# main.net
KiCad netlist of a schematic drawn in EAGLE
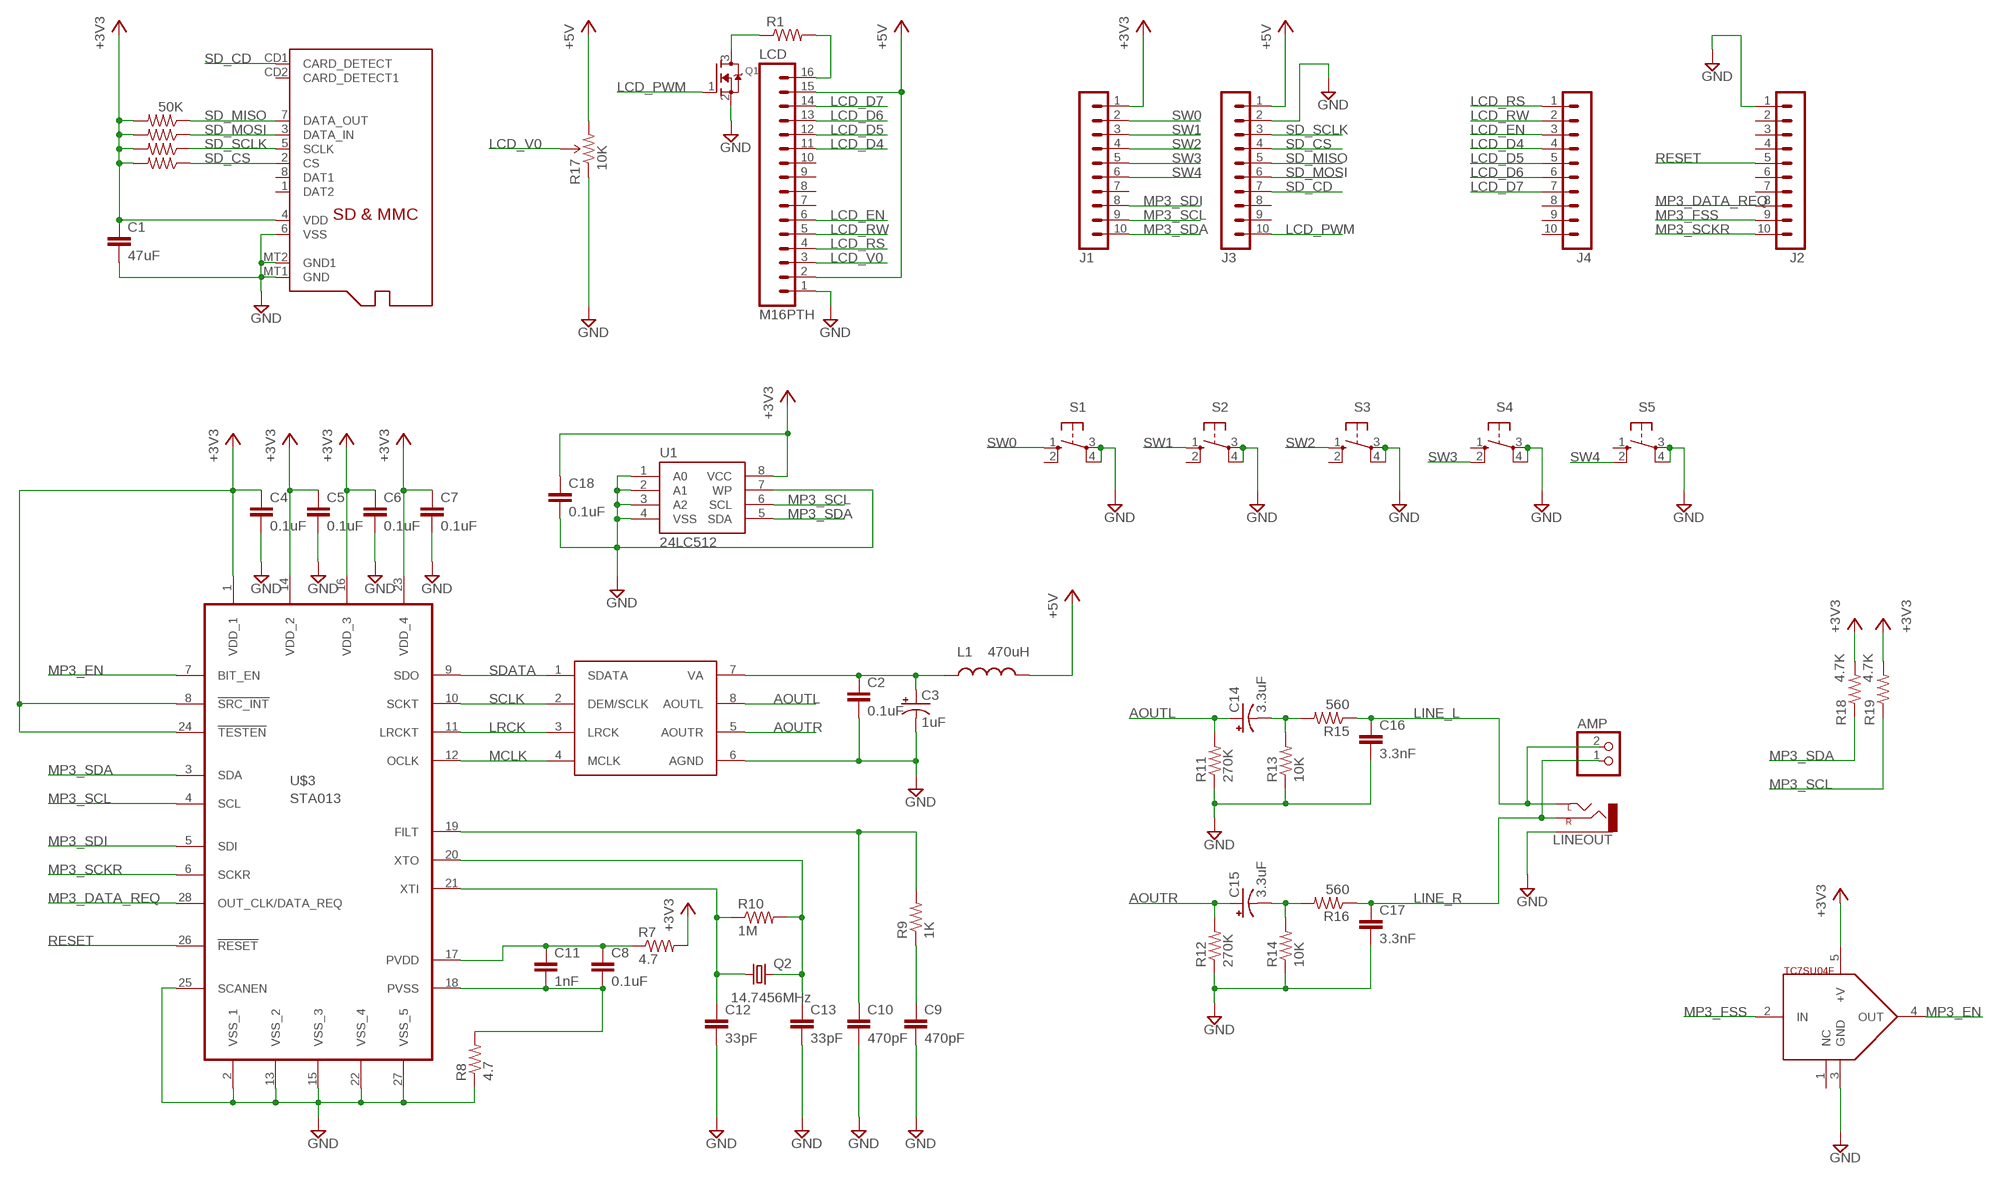
[diagram p0: schematic, sheet 1]

(export (version "E")
  (design (tool "Eeschema 10.0.6"))
  (components
    (comp (ref "AMP")
      (value "JST_2PIN-THM-RA")
      (footprint "eagle-import:JST-PH-2-THM-RA")
      (libsource (lib "eagle-import") (part "JST_2PIN-THM-RA"))
    )
    (comp (ref "C1")
      (value "47uF")
      (footprint "eagle-import:0805")
      (libsource (lib "eagle-import") (part "1.0UF-25V-+80/-20(0805)"))
    )
    (comp (ref "C2")
      (value "0.1uF")
      (footprint "eagle-import:0805")
      (libsource (lib "eagle-import") (part "1.0UF-25V-+80/-20(0805)"))
    )
    (comp (ref "C3")
      (value "1uF")
      (footprint "eagle-import:EIA3216")
      (libsource (lib "eagle-import") (part "CAP_POL1206"))
    )
    (comp (ref "C4")
      (value "0.1uF")
      (footprint "eagle-import:0805")
      (libsource (lib "eagle-import") (part "1.0UF-25V-+80/-20(0805)"))
    )
    (comp (ref "C5")
      (value "0.1uF")
      (footprint "eagle-import:0805")
      (libsource (lib "eagle-import") (part "1.0UF-25V-+80/-20(0805)"))
    )
    (comp (ref "C6")
      (value "0.1uF")
      (footprint "eagle-import:0805")
      (libsource (lib "eagle-import") (part "1.0UF-25V-+80/-20(0805)"))
    )
    (comp (ref "C7")
      (value "0.1uF")
      (footprint "eagle-import:0805")
      (libsource (lib "eagle-import") (part "1.0UF-25V-+80/-20(0805)"))
    )
    (comp (ref "C8")
      (value "0.1uF")
      (footprint "eagle-import:0805")
      (libsource (lib "eagle-import") (part "1.0UF-25V-+80/-20(0805)"))
    )
    (comp (ref "C9")
      (value "470pF")
      (footprint "eagle-import:0805")
      (libsource (lib "eagle-import") (part "1.0UF-25V-+80/-20(0805)"))
    )
    (comp (ref "C10")
      (value "470pF")
      (footprint "eagle-import:0805")
      (libsource (lib "eagle-import") (part "1.0UF-25V-+80/-20(0805)"))
    )
    (comp (ref "C11")
      (value "1nF")
      (footprint "eagle-import:0805")
      (libsource (lib "eagle-import") (part "1.0UF-25V-+80/-20(0805)"))
    )
    (comp (ref "C12")
      (value "33pF")
      (footprint "eagle-import:0805")
      (libsource (lib "eagle-import") (part "1.0UF-25V-+80/-20(0805)"))
    )
    (comp (ref "C13")
      (value "33pF")
      (footprint "eagle-import:0805")
      (libsource (lib "eagle-import") (part "1.0UF-25V-+80/-20(0805)"))
    )
    (comp (ref "C14")
      (value "3.3uF")
      (footprint "eagle-import:EIA3216")
      (libsource (lib "eagle-import") (part "CAP_POL1206"))
    )
    (comp (ref "C15")
      (value "3.3uF")
      (footprint "eagle-import:EIA3216")
      (libsource (lib "eagle-import") (part "CAP_POL1206"))
    )
    (comp (ref "C16")
      (value "3.3nF")
      (footprint "eagle-import:0805")
      (libsource (lib "eagle-import") (part "1.0UF-25V-+80/-20(0805)"))
    )
    (comp (ref "C17")
      (value "3.3nF")
      (footprint "eagle-import:0805")
      (libsource (lib "eagle-import") (part "1.0UF-25V-+80/-20(0805)"))
    )
    (comp (ref "C18")
      (value "0.1uF")
      (footprint "eagle-import:0805")
      (libsource (lib "eagle-import") (part "1.0UF-25V-+80/-20(0805)"))
    )
    (comp (ref "J1")
      (value "MA10-1")
      (footprint "eagle-import:HEADER-10")
      (libsource (lib "eagle-import") (part "MA10-1"))
    )
    (comp (ref "J2")
      (value "MA10-1")
      (footprint "eagle-import:HEADER-10")
      (libsource (lib "eagle-import") (part "MA10-1"))
    )
    (comp (ref "J3")
      (value "MA10-1")
      (footprint "eagle-import:HEADER-10")
      (libsource (lib "eagle-import") (part "MA10-1"))
    )
    (comp (ref "J4")
      (value "MA10-1")
      (footprint "eagle-import:HEADER-10")
      (libsource (lib "eagle-import") (part "MA10-1"))
    )
    (comp (ref "L1")
      (value "470uH")
      (footprint "eagle-import:SRR7032")
      (libsource (lib "eagle-import") (part "INDUCTORSRR7032"))
    )
    (comp (ref "LCD")
      (value "M16PTH")
      (footprint "eagle-import:1X16")
      (libsource (lib "eagle-import") (part "M16PTH"))
    )
    (comp (ref "LINEOUT")
      (value "AUDIO-JACKPTH")
      (footprint "eagle-import:AUDIO-JACK")
      (libsource (lib "eagle-import") (part "AUDIO-JACKPTH"))
    )
    (comp (ref "Q1")
      (value "MOSFET-NREFLOW")
      (footprint "eagle-import:SOT23")
      (libsource (lib "eagle-import") (part "MOSFET-NREFLOW"))
    )
    (comp (ref "Q2")
      (value "14.7456MHz")
      (footprint "eagle-import:HC49UP")
      (libsource (lib "eagle-import") (part "CRYSTALHC49UP"))
    )
    (comp (ref "R1")
      (value "R-US_R0805")
      (footprint "eagle-import:R0805")
      (libsource (lib "eagle-import") (part "R-US_R0805"))
    )
    (comp (ref "R3")
      (value "50K")
      (footprint "eagle-import:R0805")
      (libsource (lib "eagle-import") (part "R-US_R0805"))
    )
    (comp (ref "R4")
      (value "50K")
      (footprint "eagle-import:R0805")
      (libsource (lib "eagle-import") (part "R-US_R0805"))
    )
    (comp (ref "R5")
      (value "50K")
      (footprint "eagle-import:R0805")
      (libsource (lib "eagle-import") (part "R-US_R0805"))
    )
    (comp (ref "R6")
      (value "50K")
      (footprint "eagle-import:R0805")
      (libsource (lib "eagle-import") (part "R-US_R0805"))
    )
    (comp (ref "R7")
      (value "4.7")
      (footprint "eagle-import:R0805")
      (libsource (lib "eagle-import") (part "R-US_R0805"))
    )
    (comp (ref "R8")
      (value "4.7")
      (footprint "eagle-import:R0805")
      (libsource (lib "eagle-import") (part "R-US_R0805"))
    )
    (comp (ref "R9")
      (value "1K")
      (footprint "eagle-import:R0805")
      (libsource (lib "eagle-import") (part "R-US_R0805"))
    )
    (comp (ref "R10")
      (value "1M")
      (footprint "eagle-import:R0805")
      (libsource (lib "eagle-import") (part "R-US_R0805"))
    )
    (comp (ref "R11")
      (value "270K")
      (footprint "eagle-import:R0805")
      (libsource (lib "eagle-import") (part "R-US_R0805"))
    )
    (comp (ref "R12")
      (value "270K")
      (footprint "eagle-import:R0805")
      (libsource (lib "eagle-import") (part "R-US_R0805"))
    )
    (comp (ref "R13")
      (value "10K")
      (footprint "eagle-import:R0805")
      (libsource (lib "eagle-import") (part "R-US_R0805"))
    )
    (comp (ref "R14")
      (value "10K")
      (footprint "eagle-import:R0805")
      (libsource (lib "eagle-import") (part "R-US_R0805"))
    )
    (comp (ref "R15")
      (value "560")
      (footprint "eagle-import:R0805")
      (libsource (lib "eagle-import") (part "R-US_R0805"))
    )
    (comp (ref "R16")
      (value "560")
      (footprint "eagle-import:R0805")
      (libsource (lib "eagle-import") (part "R-US_R0805"))
    )
    (comp (ref "R17")
      (value "10K")
      (footprint "eagle-import:3364W")
      (libsource (lib "eagle-import") (part "TRIMPOT3364W"))
    )
    (comp (ref "R18")
      (value "4.7K")
      (footprint "eagle-import:R0805")
      (libsource (lib "eagle-import") (part "R-US_R0805"))
    )
    (comp (ref "R19")
      (value "4.7K")
      (footprint "eagle-import:R0805")
      (libsource (lib "eagle-import") (part "R-US_R0805"))
    )
    (comp (ref "S1")
      (value "10-XX")
      (footprint "eagle-import:B3F-10XX")
      (fields (field (name "MPN") "B3F-1000"))
      (libsource (lib "eagle-import") (part "10-XX"))
    )
    (comp (ref "S2")
      (value "10-XX")
      (footprint "eagle-import:B3F-10XX")
      (fields (field (name "MPN") "B3F-1000"))
      (libsource (lib "eagle-import") (part "10-XX"))
    )
    (comp (ref "S3")
      (value "10-XX")
      (footprint "eagle-import:B3F-10XX")
      (fields (field (name "MPN") "B3F-1000"))
      (libsource (lib "eagle-import") (part "10-XX"))
    )
    (comp (ref "S4")
      (value "10-XX")
      (footprint "eagle-import:B3F-10XX")
      (fields (field (name "MPN") "B3F-1000"))
      (libsource (lib "eagle-import") (part "10-XX"))
    )
    (comp (ref "S5")
      (value "10-XX")
      (footprint "eagle-import:B3F-10XX")
      (fields (field (name "MPN") "B3F-1000"))
      (libsource (lib "eagle-import") (part "10-XX"))
    )
    (comp (ref "U$1")
      (value "MICROSD")
      (footprint "eagle-import:MICROSD")
      (libsource (lib "eagle-import") (part "MICROSD"))
    )
    (comp (ref "U$2")
      (value "CS4334")
      (footprint "eagle-import:SO08")
      (libsource (lib "eagle-import") (part "CS4334"))
    )
    (comp (ref "U$3")
      (value "STA013")
      (footprint "eagle-import:SO28W")
      (libsource (lib "eagle-import") (part "STA013"))
    )
    (comp (ref "U$4")
      (value "TC7SU04F")
      (footprint "eagle-import:SOT23-5")
      (libsource (lib "eagle-import") (part "TC7SU04F"))
    )
    (comp (ref "U1")
      (value "24LC512")
      (footprint "eagle-import:SO08")
      (libsource (lib "eagle-import") (part "EEPROM-I2CSMD"))
    )
  )
  (nets
    (net (code "1") (name "+3V3") (class "Default")
      (node (ref "C1") (pin "1") (pinfunction "1_1") (pintype "passive"))
      (node (ref "C18") (pin "1") (pinfunction "1_1") (pintype "passive"))
      (node (ref "C4") (pin "1") (pinfunction "1_1") (pintype "passive"))
      (node (ref "C5") (pin "1") (pinfunction "1_1") (pintype "passive"))
      (node (ref "C6") (pin "1") (pinfunction "1_1") (pintype "passive"))
      (node (ref "C7") (pin "1") (pinfunction "1_1") (pintype "passive"))
      (node (ref "J1") (pin "1") (pinfunction "1_1") (pintype "passive"))
      (node (ref "R18") (pin "2") (pinfunction "2_2") (pintype "passive"))
      (node (ref "R19") (pin "2") (pinfunction "2_2") (pintype "passive"))
      (node (ref "R3") (pin "2") (pinfunction "2_2") (pintype "passive"))
      (node (ref "R4") (pin "2") (pinfunction "2_2") (pintype "passive"))
      (node (ref "R5") (pin "2") (pinfunction "2_2") (pintype "passive"))
      (node (ref "R6") (pin "2") (pinfunction "2_2") (pintype "passive"))
      (node (ref "R7") (pin "2") (pinfunction "2_2") (pintype "passive"))
      (node (ref "U$1") (pin "4") (pinfunction "VDD_4") (pintype "power_in"))
      (node (ref "U$3") (pin "1") (pinfunction "VDD_1_1") (pintype "bidirectional"))
      (node (ref "U$3") (pin "14") (pinfunction "VDD_2_14") (pintype "bidirectional"))
      (node (ref "U$3") (pin "16") (pinfunction "VDD_3_16") (pintype "bidirectional"))
      (node (ref "U$3") (pin "23") (pinfunction "VDD_4_23") (pintype "bidirectional"))
      (node (ref "U$3") (pin "24") (pinfunction "~{TESTEN}_24") (pintype "bidirectional"))
      (node (ref "U$3") (pin "8") (pinfunction "~{SRC_INT}_8") (pintype "bidirectional"))
      (node (ref "U$4") (pin "5") (pinfunction "+V_5") (pintype "bidirectional"))
      (node (ref "U1") (pin "8") (pinfunction "VCC_8") (pintype "power_in"))
    )
    (net (code "2") (name "+5V") (class "Default")
      (node (ref "J3") (pin "1") (pinfunction "1_1") (pintype "passive"))
      (node (ref "L1") (pin "P$2") (pinfunction "2_P$2") (pintype "passive"))
      (node (ref "LCD") (pin "15") (pinfunction "15_15") (pintype "passive"))
      (node (ref "LCD") (pin "2") (pinfunction "2_2") (pintype "passive"))
      (node (ref "R17") (pin "3") (pinfunction "CW_3") (pintype "passive"))
    )
    (net (code "3") (name "/AOUTL") (class "Default")
      (node (ref "C14") (pin "A") (pinfunction "+_A") (pintype "passive"))
      (node (ref "R11") (pin "2") (pinfunction "2_2") (pintype "passive"))
      (node (ref "U$2") (pin "8") (pinfunction "AOUTL_8") (pintype "bidirectional"))
    )
    (net (code "4") (name "/AOUTR") (class "Default")
      (node (ref "C15") (pin "A") (pinfunction "+_A") (pintype "passive"))
      (node (ref "R12") (pin "2") (pinfunction "2_2") (pintype "passive"))
      (node (ref "U$2") (pin "5") (pinfunction "AOUTR_5") (pintype "bidirectional"))
    )
    (net (code "5") (name "/LCD_D4") (class "Default")
      (node (ref "J4") (pin "4") (pinfunction "4_4") (pintype "passive"))
      (node (ref "LCD") (pin "11") (pinfunction "11_11") (pintype "passive"))
    )
    (net (code "6") (name "/LCD_D5") (class "Default")
      (node (ref "J4") (pin "5") (pinfunction "5_5") (pintype "passive"))
      (node (ref "LCD") (pin "12") (pinfunction "12_12") (pintype "passive"))
    )
    (net (code "7") (name "/LCD_D6") (class "Default")
      (node (ref "J4") (pin "6") (pinfunction "6_6") (pintype "passive"))
      (node (ref "LCD") (pin "13") (pinfunction "13_13") (pintype "passive"))
    )
    (net (code "8") (name "/LCD_D7") (class "Default")
      (node (ref "J4") (pin "7") (pinfunction "7_7") (pintype "passive"))
      (node (ref "LCD") (pin "14") (pinfunction "14_14") (pintype "passive"))
    )
    (net (code "9") (name "/LCD_EN") (class "Default")
      (node (ref "J4") (pin "3") (pinfunction "3_3") (pintype "passive"))
      (node (ref "LCD") (pin "6") (pinfunction "6_6") (pintype "passive"))
    )
    (net (code "10") (name "/LCD_PWM") (class "Default")
      (node (ref "J3") (pin "10") (pinfunction "10_10") (pintype "passive"))
      (node (ref "Q1") (pin "1") (pinfunction "G_1") (pintype "bidirectional"))
    )
    (net (code "11") (name "/LCD_RS") (class "Default")
      (node (ref "J4") (pin "1") (pinfunction "1_1") (pintype "passive"))
      (node (ref "LCD") (pin "4") (pinfunction "4_4") (pintype "passive"))
    )
    (net (code "12") (name "/LCD_RW") (class "Default")
      (node (ref "J4") (pin "2") (pinfunction "2_2") (pintype "passive"))
      (node (ref "LCD") (pin "5") (pinfunction "5_5") (pintype "passive"))
    )
    (net (code "13") (name "/LCD_V0") (class "Default")
      (node (ref "LCD") (pin "3") (pinfunction "3_3") (pintype "passive"))
      (node (ref "R17") (pin "2") (pinfunction "WIPER_2") (pintype "passive"))
    )
    (net (code "14") (name "/LINE_L") (class "Default")
      (node (ref "AMP") (pin "2") (pinfunction "1_2") (pintype "passive"))
      (node (ref "C16") (pin "1") (pinfunction "1_1") (pintype "passive"))
      (node (ref "LINEOUT") (pin "TIP") (pinfunction "LEFT_TIP") (pintype "bidirectional"))
      (node (ref "R15") (pin "1") (pinfunction "1_1") (pintype "passive"))
    )
    (net (code "15") (name "/LINE_R") (class "Default")
      (node (ref "AMP") (pin "1") (pinfunction "2_1") (pintype "passive"))
      (node (ref "C17") (pin "1") (pinfunction "1_1") (pintype "passive"))
      (node (ref "LINEOUT") (pin "RING") (pinfunction "RIGHT_RING") (pintype "bidirectional"))
      (node (ref "R16") (pin "1") (pinfunction "1_1") (pintype "passive"))
    )
    (net (code "16") (name "/LRCK") (class "Default")
      (node (ref "U$2") (pin "3") (pinfunction "LRCK_3") (pintype "bidirectional"))
      (node (ref "U$3") (pin "11") (pinfunction "LRCKT_11") (pintype "bidirectional"))
    )
    (net (code "17") (name "/MCLK") (class "Default")
      (node (ref "U$2") (pin "4") (pinfunction "MCLK_4") (pintype "bidirectional"))
      (node (ref "U$3") (pin "12") (pinfunction "OCLK_12") (pintype "bidirectional"))
    )
    (net (code "18") (name "/MP3_DATA_REQ") (class "Default")
      (node (ref "J2") (pin "8") (pinfunction "8_8") (pintype "passive"))
      (node (ref "U$3") (pin "28") (pinfunction "OUT_CLK/DATA_REQ_28") (pintype "bidirectional"))
    )
    (net (code "19") (name "/MP3_EN") (class "Default")
      (node (ref "U$3") (pin "7") (pinfunction "BIT_EN_7") (pintype "bidirectional"))
      (node (ref "U$4") (pin "4") (pinfunction "OUT_4") (pintype "bidirectional"))
    )
    (net (code "20") (name "/MP3_FSS") (class "Default")
      (node (ref "J2") (pin "9") (pinfunction "9_9") (pintype "passive"))
      (node (ref "U$4") (pin "2") (pinfunction "IN_2") (pintype "bidirectional"))
    )
    (net (code "21") (name "/MP3_SCKR") (class "Default")
      (node (ref "J2") (pin "10") (pinfunction "10_10") (pintype "passive"))
      (node (ref "U$3") (pin "6") (pinfunction "SCKR_6") (pintype "bidirectional"))
    )
    (net (code "22") (name "/MP3_SCL") (class "Default")
      (node (ref "J1") (pin "9") (pinfunction "9_9") (pintype "passive"))
      (node (ref "R19") (pin "1") (pinfunction "1_1") (pintype "passive"))
      (node (ref "U$3") (pin "4") (pinfunction "SCL_4") (pintype "bidirectional"))
      (node (ref "U1") (pin "6") (pinfunction "SCL_6") (pintype "bidirectional"))
    )
    (net (code "23") (name "/MP3_SDA") (class "Default")
      (node (ref "J1") (pin "10") (pinfunction "10_10") (pintype "passive"))
      (node (ref "R18") (pin "1") (pinfunction "1_1") (pintype "passive"))
      (node (ref "U$3") (pin "3") (pinfunction "SDA_3") (pintype "bidirectional"))
      (node (ref "U1") (pin "5") (pinfunction "SDA_5") (pintype "bidirectional"))
    )
    (net (code "24") (name "/MP3_SDI") (class "Default")
      (node (ref "J1") (pin "8") (pinfunction "8_8") (pintype "passive"))
      (node (ref "U$3") (pin "5") (pinfunction "SDI_5") (pintype "bidirectional"))
    )
    (net (code "25") (name "/RESET") (class "Default")
      (node (ref "J2") (pin "5") (pinfunction "5_5") (pintype "passive"))
      (node (ref "U$3") (pin "26") (pinfunction "~{RESET}_26") (pintype "bidirectional"))
    )
    (net (code "26") (name "/SCLK") (class "Default")
      (node (ref "U$2") (pin "2") (pinfunction "DEM/SCLK_2") (pintype "bidirectional"))
      (node (ref "U$3") (pin "10") (pinfunction "SCKT_10") (pintype "bidirectional"))
    )
    (net (code "27") (name "/SDATA") (class "Default")
      (node (ref "U$2") (pin "1") (pinfunction "SDATA_1") (pintype "bidirectional"))
      (node (ref "U$3") (pin "9") (pinfunction "SDO_9") (pintype "bidirectional"))
    )
    (net (code "28") (name "/SD_CD") (class "Default")
      (node (ref "J3") (pin "7") (pinfunction "7_7") (pintype "passive"))
      (node (ref "U$1") (pin "CD1") (pinfunction "CARD_DETECT_CD1") (pintype "passive"))
    )
    (net (code "29") (name "/SD_CS") (class "Default")
      (node (ref "J3") (pin "4") (pinfunction "4_4") (pintype "passive"))
      (node (ref "R6") (pin "1") (pinfunction "1_1") (pintype "passive"))
      (node (ref "U$1") (pin "2") (pinfunction "CS_2") (pintype "input"))
    )
    (net (code "30") (name "/SD_MISO") (class "Default")
      (node (ref "J3") (pin "5") (pinfunction "5_5") (pintype "passive"))
      (node (ref "R3") (pin "1") (pinfunction "1_1") (pintype "passive"))
      (node (ref "U$1") (pin "7") (pinfunction "DATA_OUT_7") (pintype "output"))
    )
    (net (code "31") (name "/SD_MOSI") (class "Default")
      (node (ref "J3") (pin "6") (pinfunction "6_6") (pintype "passive"))
      (node (ref "R4") (pin "1") (pinfunction "1_1") (pintype "passive"))
      (node (ref "U$1") (pin "3") (pinfunction "DATA_IN_3") (pintype "input"))
    )
    (net (code "32") (name "/SD_SCLK") (class "Default")
      (node (ref "J3") (pin "3") (pinfunction "3_3") (pintype "passive"))
      (node (ref "R5") (pin "1") (pinfunction "1_1") (pintype "passive"))
      (node (ref "U$1") (pin "5") (pinfunction "SCLK_5") (pintype "input"))
    )
    (net (code "33") (name "/SW0") (class "Default")
      (node (ref "J1") (pin "2") (pinfunction "2_2") (pintype "passive"))
      (node (ref "S1") (pin "1") (pinfunction "S_1") (pintype "passive"))
    )
    (net (code "34") (name "/SW1") (class "Default")
      (node (ref "J1") (pin "3") (pinfunction "3_3") (pintype "passive"))
      (node (ref "S2") (pin "1") (pinfunction "S_1") (pintype "passive"))
    )
    (net (code "35") (name "/SW2") (class "Default")
      (node (ref "J1") (pin "4") (pinfunction "4_4") (pintype "passive"))
      (node (ref "S3") (pin "1") (pinfunction "S_1") (pintype "passive"))
    )
    (net (code "36") (name "/SW3") (class "Default")
      (node (ref "J1") (pin "5") (pinfunction "5_5") (pintype "passive"))
      (node (ref "S4") (pin "2") (pinfunction "S1_2") (pintype "passive"))
    )
    (net (code "37") (name "/SW4") (class "Default")
      (node (ref "J1") (pin "6") (pinfunction "6_6") (pintype "passive"))
      (node (ref "S5") (pin "2") (pinfunction "S1_2") (pintype "passive"))
    )
    (net (code "38") (name "GND") (class "Default")
      (node (ref "C1") (pin "2") (pinfunction "2_2") (pintype "passive"))
      (node (ref "C10") (pin "2") (pinfunction "2_2") (pintype "passive"))
      (node (ref "C12") (pin "2") (pinfunction "2_2") (pintype "passive"))
      (node (ref "C13") (pin "2") (pinfunction "2_2") (pintype "passive"))
      (node (ref "C16") (pin "2") (pinfunction "2_2") (pintype "passive"))
      (node (ref "C17") (pin "2") (pinfunction "2_2") (pintype "passive"))
      (node (ref "C18") (pin "2") (pinfunction "2_2") (pintype "passive"))
      (node (ref "C2") (pin "2") (pinfunction "2_2") (pintype "passive"))
      (node (ref "C3") (pin "C") (pinfunction "-_C") (pintype "passive"))
      (node (ref "C4") (pin "2") (pinfunction "2_2") (pintype "passive"))
      (node (ref "C5") (pin "2") (pinfunction "2_2") (pintype "passive"))
      (node (ref "C6") (pin "2") (pinfunction "2_2") (pintype "passive"))
      (node (ref "C7") (pin "2") (pinfunction "2_2") (pintype "passive"))
      (node (ref "C9") (pin "2") (pinfunction "2_2") (pintype "passive"))
      (node (ref "J2") (pin "1") (pinfunction "1_1") (pintype "passive"))
      (node (ref "J3") (pin "2") (pinfunction "2_2") (pintype "passive"))
      (node (ref "LCD") (pin "1") (pinfunction "1_1") (pintype "passive"))
      (node (ref "LINEOUT") (pin "SLEEVE") (pinfunction "SLEEVE_SLEEVE") (pintype "bidirectional"))
      (node (ref "Q1") (pin "2") (pinfunction "S_2") (pintype "bidirectional"))
      (node (ref "R11") (pin "1") (pinfunction "1_1") (pintype "passive"))
      (node (ref "R12") (pin "1") (pinfunction "1_1") (pintype "passive"))
      (node (ref "R13") (pin "1") (pinfunction "1_1") (pintype "passive"))
      (node (ref "R14") (pin "1") (pinfunction "1_1") (pintype "passive"))
      (node (ref "R17") (pin "1") (pinfunction "CCW_1") (pintype "passive"))
      (node (ref "R8") (pin "1") (pinfunction "1_1") (pintype "passive"))
      (node (ref "S1") (pin "3") (pinfunction "P_3") (pintype "passive"))
      (node (ref "S1") (pin "4") (pinfunction "P1_4") (pintype "passive"))
      (node (ref "S2") (pin "3") (pinfunction "P_3") (pintype "passive"))
      (node (ref "S2") (pin "4") (pinfunction "P1_4") (pintype "passive"))
      (node (ref "S3") (pin "3") (pinfunction "P_3") (pintype "passive"))
      (node (ref "S3") (pin "4") (pinfunction "P1_4") (pintype "passive"))
      (node (ref "S4") (pin "3") (pinfunction "P_3") (pintype "passive"))
      (node (ref "S4") (pin "4") (pinfunction "P1_4") (pintype "passive"))
      (node (ref "S5") (pin "3") (pinfunction "P_3") (pintype "passive"))
      (node (ref "S5") (pin "4") (pinfunction "P1_4") (pintype "passive"))
      (node (ref "U$1") (pin "6") (pinfunction "VSS_6") (pintype "power_in"))
      (node (ref "U$1") (pin "MT1") (pinfunction "GND_MT1") (pintype "power_in"))
      (node (ref "U$1") (pin "MT2") (pinfunction "GND1_MT2") (pintype "power_in"))
      (node (ref "U$2") (pin "6") (pinfunction "AGND_6") (pintype "bidirectional"))
      (node (ref "U$3") (pin "13") (pinfunction "VSS_2_13") (pintype "bidirectional"))
      (node (ref "U$3") (pin "15") (pinfunction "VSS_3_15") (pintype "bidirectional"))
      (node (ref "U$3") (pin "2") (pinfunction "VSS_1_2") (pintype "bidirectional"))
      (node (ref "U$3") (pin "22") (pinfunction "VSS_4_22") (pintype "bidirectional"))
      (node (ref "U$3") (pin "25") (pinfunction "SCANEN_25") (pintype "bidirectional"))
      (node (ref "U$3") (pin "27") (pinfunction "VSS_5_27") (pintype "bidirectional"))
      (node (ref "U$4") (pin "3") (pinfunction "GND_3") (pintype "bidirectional"))
      (node (ref "U1") (pin "1") (pinfunction "A0_1") (pintype "bidirectional"))
      (node (ref "U1") (pin "2") (pinfunction "A1_2") (pintype "bidirectional"))
      (node (ref "U1") (pin "3") (pinfunction "A2_3") (pintype "bidirectional"))
      (node (ref "U1") (pin "4") (pinfunction "VSS_4") (pintype "power_in"))
      (node (ref "U1") (pin "7") (pinfunction "WP_7") (pintype "bidirectional"))
    )
    (net (code "39") (name "Net-(C3-+)") (class "Default")
      (node (ref "C2") (pin "1") (pinfunction "1_1") (pintype "passive"))
      (node (ref "C3") (pin "A") (pinfunction "+_A") (pintype "passive"))
      (node (ref "L1") (pin "P$1") (pinfunction "1_P$1") (pintype "passive"))
      (node (ref "U$2") (pin "7") (pinfunction "VA_7") (pintype "bidirectional"))
    )
    (net (code "40") (name "Net-(C9-Pad1)") (class "Default")
      (node (ref "C9") (pin "1") (pinfunction "1_1") (pintype "passive"))
      (node (ref "R9") (pin "1") (pinfunction "1_1") (pintype "passive"))
    )
    (net (code "41") (name "Net-(C14--)") (class "Default")
      (node (ref "C14") (pin "C") (pinfunction "-_C") (pintype "passive"))
      (node (ref "R13") (pin "2") (pinfunction "2_2") (pintype "passive"))
      (node (ref "R15") (pin "2") (pinfunction "2_2") (pintype "passive"))
    )
    (net (code "42") (name "Net-(C15--)") (class "Default")
      (node (ref "C15") (pin "C") (pinfunction "-_C") (pintype "passive"))
      (node (ref "R14") (pin "2") (pinfunction "2_2") (pintype "passive"))
      (node (ref "R16") (pin "2") (pinfunction "2_2") (pintype "passive"))
    )
    (net (code "43") (name "Net-(LCD-Pad16)") (class "Default")
      (node (ref "LCD") (pin "16") (pinfunction "16_16") (pintype "passive"))
      (node (ref "R1") (pin "2") (pinfunction "2_2") (pintype "passive"))
    )
    (net (code "44") (name "Net-(Q1-D)") (class "Default")
      (node (ref "Q1") (pin "3") (pinfunction "D_3") (pintype "bidirectional"))
      (node (ref "R1") (pin "1") (pinfunction "1_1") (pintype "passive"))
    )
    (net (code "45") (name "Net-(U$3-FILT)") (class "Default")
      (node (ref "C10") (pin "1") (pinfunction "1_1") (pintype "passive"))
      (node (ref "R9") (pin "2") (pinfunction "2_2") (pintype "passive"))
      (node (ref "U$3") (pin "19") (pinfunction "FILT_19") (pintype "bidirectional"))
    )
    (net (code "46") (name "Net-(U$3-PVDD)") (class "Default")
      (node (ref "C11") (pin "1") (pinfunction "1_1") (pintype "passive"))
      (node (ref "C8") (pin "1") (pinfunction "1_1") (pintype "passive"))
      (node (ref "R7") (pin "1") (pinfunction "1_1") (pintype "passive"))
      (node (ref "U$3") (pin "17") (pinfunction "PVDD_17") (pintype "bidirectional"))
    )
    (net (code "47") (name "Net-(U$3-PVSS)") (class "Default")
      (node (ref "C11") (pin "2") (pinfunction "2_2") (pintype "passive"))
      (node (ref "C8") (pin "2") (pinfunction "2_2") (pintype "passive"))
      (node (ref "R8") (pin "2") (pinfunction "2_2") (pintype "passive"))
      (node (ref "U$3") (pin "18") (pinfunction "PVSS_18") (pintype "bidirectional"))
    )
    (net (code "48") (name "Net-(U$3-XTI)") (class "Default")
      (node (ref "C12") (pin "1") (pinfunction "1_1") (pintype "passive"))
      (node (ref "Q2") (pin "1") (pinfunction "1_1") (pintype "passive"))
      (node (ref "R10") (pin "1") (pinfunction "1_1") (pintype "passive"))
      (node (ref "U$3") (pin "21") (pinfunction "XTI_21") (pintype "bidirectional"))
    )
    (net (code "49") (name "Net-(U$3-XTO)") (class "Default")
      (node (ref "C13") (pin "1") (pinfunction "1_1") (pintype "passive"))
      (node (ref "Q2") (pin "2") (pinfunction "2_2") (pintype "passive"))
      (node (ref "R10") (pin "2") (pinfunction "2_2") (pintype "passive"))
      (node (ref "U$3") (pin "20") (pinfunction "XTO_20") (pintype "bidirectional"))
    )
    (net (code "50") (name "unconnected-(J1-Pad7)") (class "Default")
      (node (ref "J1") (pin "7") (pinfunction "7_7") (pintype "passive"))
    )
    (net (code "51") (name "unconnected-(J2-Pad2)") (class "Default")
      (node (ref "J2") (pin "2") (pinfunction "2_2") (pintype "passive"))
    )
    (net (code "52") (name "unconnected-(J2-Pad3)") (class "Default")
      (node (ref "J2") (pin "3") (pinfunction "3_3") (pintype "passive"))
    )
    (net (code "53") (name "unconnected-(J2-Pad4)") (class "Default")
      (node (ref "J2") (pin "4") (pinfunction "4_4") (pintype "passive"))
    )
    (net (code "54") (name "unconnected-(J2-Pad6)") (class "Default")
      (node (ref "J2") (pin "6") (pinfunction "6_6") (pintype "passive"))
    )
    (net (code "55") (name "unconnected-(J2-Pad7)") (class "Default")
      (node (ref "J2") (pin "7") (pinfunction "7_7") (pintype "passive"))
    )
    (net (code "56") (name "unconnected-(J3-Pad8)") (class "Default")
      (node (ref "J3") (pin "8") (pinfunction "8_8") (pintype "passive"))
    )
    (net (code "57") (name "unconnected-(J3-Pad9)") (class "Default")
      (node (ref "J3") (pin "9") (pinfunction "9_9") (pintype "passive"))
    )
    (net (code "58") (name "unconnected-(J4-Pad8)") (class "Default")
      (node (ref "J4") (pin "8") (pinfunction "8_8") (pintype "passive"))
    )
    (net (code "59") (name "unconnected-(J4-Pad9)") (class "Default")
      (node (ref "J4") (pin "9") (pinfunction "9_9") (pintype "passive"))
    )
    (net (code "60") (name "unconnected-(J4-Pad10)") (class "Default")
      (node (ref "J4") (pin "10") (pinfunction "10_10") (pintype "passive"))
    )
    (net (code "61") (name "unconnected-(LCD-Pad7)") (class "Default")
      (node (ref "LCD") (pin "7") (pinfunction "7_7") (pintype "passive"))
    )
    (net (code "62") (name "unconnected-(LCD-Pad8)") (class "Default")
      (node (ref "LCD") (pin "8") (pinfunction "8_8") (pintype "passive"))
    )
    (net (code "63") (name "unconnected-(LCD-Pad9)") (class "Default")
      (node (ref "LCD") (pin "9") (pinfunction "9_9") (pintype "passive"))
    )
    (net (code "64") (name "unconnected-(LCD-Pad10)") (class "Default")
      (node (ref "LCD") (pin "10") (pinfunction "10_10") (pintype "passive"))
    )
    (net (code "65") (name "unconnected-(S1-S1-Pad2)") (class "Default")
      (node (ref "S1") (pin "2") (pinfunction "S1_2") (pintype "passive"))
    )
    (net (code "66") (name "unconnected-(S2-S1-Pad2)") (class "Default")
      (node (ref "S2") (pin "2") (pinfunction "S1_2") (pintype "passive"))
    )
    (net (code "67") (name "unconnected-(S3-S1-Pad2)") (class "Default")
      (node (ref "S3") (pin "2") (pinfunction "S1_2") (pintype "passive"))
    )
    (net (code "68") (name "unconnected-(S4-S-Pad1)") (class "Default")
      (node (ref "S4") (pin "1") (pinfunction "S_1") (pintype "passive"))
    )
    (net (code "69") (name "unconnected-(S5-S-Pad1)") (class "Default")
      (node (ref "S5") (pin "1") (pinfunction "S_1") (pintype "passive"))
    )
    (net (code "70") (name "unconnected-(U$1-CARD_DETECT1-PadCD2)") (class "Default")
      (node (ref "U$1") (pin "CD2") (pinfunction "CARD_DETECT1_CD2") (pintype "passive"))
    )
    (net (code "71") (name "unconnected-(U$1-DAT1-Pad8)") (class "Default")
      (node (ref "U$1") (pin "8") (pinfunction "DAT1_8") (pintype "bidirectional"))
    )
    (net (code "72") (name "unconnected-(U$1-DAT2-Pad1)") (class "Default")
      (node (ref "U$1") (pin "1") (pinfunction "DAT2_1") (pintype "bidirectional"))
    )
    (net (code "73") (name "unconnected-(U$4-NC-Pad1)") (class "Default")
      (node (ref "U$4") (pin "1") (pinfunction "NC_1") (pintype "bidirectional"))
    )
  )
)
